# endstop_ctl.net
KiCad netlist of a schematic drawn in EAGLE
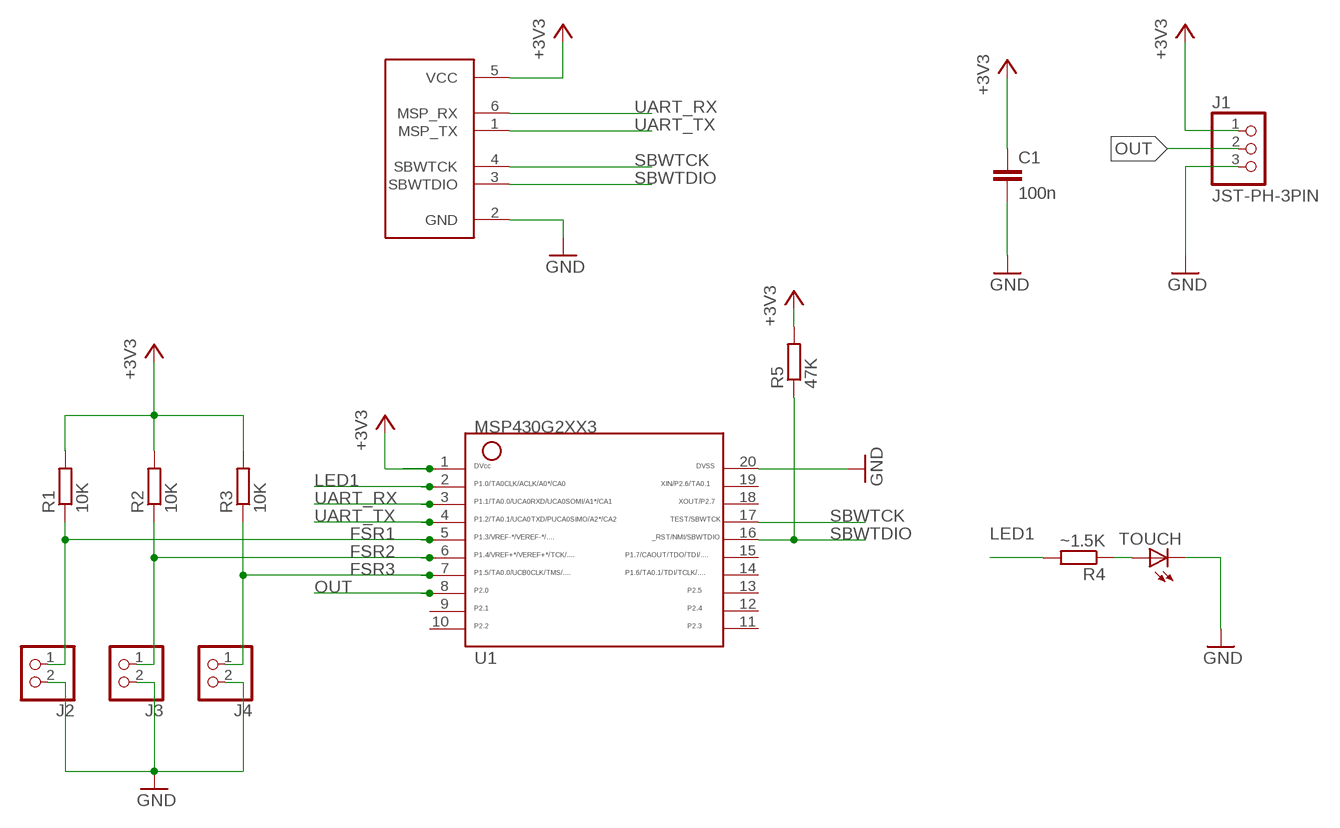
[diagram p0: schematic, sheet 1]

(export (version "E")
  (design (tool "Eeschema 10.0.6"))
  (components
    (comp (ref "C1")
      (value "100n")
      (footprint "eagle-import:C0603")
      (libsource (lib "eagle-import") (part "C-EUC0603"))
    )
    (comp (ref "J1")
      (value "JST-PH-3PIN")
      (footprint "eagle-import:JST-PH-3PIN-PTH-RA")
      (libsource (lib "eagle-import") (part "JST-PH-3PIN"))
    )
    (comp (ref "J2")
      (value "JST_2PIN-THM-RA")
      (footprint "eagle-import:JST-PH-2-THM-RA")
      (libsource (lib "eagle-import") (part "JST_2PIN-THM-RA"))
    )
    (comp (ref "J3")
      (value "JST_2PIN-THM-RA")
      (footprint "eagle-import:JST-PH-2-THM-RA")
      (libsource (lib "eagle-import") (part "JST_2PIN-THM-RA"))
    )
    (comp (ref "J4")
      (value "JST_2PIN-THM-RA")
      (footprint "eagle-import:JST-PH-2-THM-RA")
      (libsource (lib "eagle-import") (part "JST_2PIN-THM-RA"))
    )
    (comp (ref "J5")
      (value "MSP-SBWPTH")
      (footprint "eagle-import:MSP-SBW-0.05-PTH-90DEG")
      (libsource (lib "eagle-import") (part "MSP-SBWPTH"))
    )
    (comp (ref "R1")
      (value "10K")
      (footprint "eagle-import:R0603")
      (libsource (lib "eagle-import") (part "R-EU_R0603"))
    )
    (comp (ref "R2")
      (value "10K")
      (footprint "eagle-import:R0603")
      (libsource (lib "eagle-import") (part "R-EU_R0603"))
    )
    (comp (ref "R3")
      (value "10K")
      (footprint "eagle-import:R0603")
      (libsource (lib "eagle-import") (part "R-EU_R0603"))
    )
    (comp (ref "R4")
      (value "~1.5K")
      (footprint "eagle-import:R0603")
      (libsource (lib "eagle-import") (part "R-EU_R0603"))
    )
    (comp (ref "R5")
      (value "47K")
      (footprint "eagle-import:R0603")
      (libsource (lib "eagle-import") (part "R-EU_R0603"))
    )
    (comp (ref "TOUCH")
      (value "LED0603")
      (footprint "eagle-import:LED-0603")
      (libsource (lib "eagle-import") (part "LED0603"))
    )
    (comp (ref "U1")
      (value "G2XX3---PW20")
      (footprint "eagle-import:PW20")
      (libsource (lib "eagle-import") (part "G2XX3---PW20"))
    )
  )
  (nets
    (net (code "1") (name "+3V3") (class "Default")
      (node (ref "C1") (pin "1") (pinfunction "1_1") (pintype "passive"))
      (node (ref "J1") (pin "1") (pinfunction "1_1") (pintype "passive"))
      (node (ref "J5") (pin "5") (pinfunction "VCC_5") (pintype "power_in"))
      (node (ref "R1") (pin "2") (pinfunction "2_2") (pintype "passive"))
      (node (ref "R2") (pin "2") (pinfunction "2_2") (pintype "passive"))
      (node (ref "R3") (pin "2") (pinfunction "2_2") (pintype "passive"))
      (node (ref "R5") (pin "2") (pinfunction "2_2") (pintype "passive"))
      (node (ref "U1") (pin "1") (pinfunction "1_1") (pintype "bidirectional"))
    )
    (net (code "2") (name "/FSR1") (class "Default")
      (node (ref "J2") (pin "1") (pinfunction "2_1") (pintype "passive"))
      (node (ref "R1") (pin "1") (pinfunction "1_1") (pintype "passive"))
      (node (ref "U1") (pin "5") (pinfunction "5_5") (pintype "bidirectional"))
    )
    (net (code "3") (name "/FSR2") (class "Default")
      (node (ref "J3") (pin "1") (pinfunction "2_1") (pintype "passive"))
      (node (ref "R2") (pin "1") (pinfunction "1_1") (pintype "passive"))
      (node (ref "U1") (pin "6") (pinfunction "6_6") (pintype "bidirectional"))
    )
    (net (code "4") (name "/FSR3") (class "Default")
      (node (ref "J4") (pin "1") (pinfunction "2_1") (pintype "passive"))
      (node (ref "R3") (pin "1") (pinfunction "1_1") (pintype "passive"))
      (node (ref "U1") (pin "7") (pinfunction "7_7") (pintype "bidirectional"))
    )
    (net (code "5") (name "/LED1") (class "Default")
      (node (ref "R4") (pin "2") (pinfunction "2_2") (pintype "passive"))
      (node (ref "U1") (pin "2") (pinfunction "2_2") (pintype "bidirectional"))
    )
    (net (code "6") (name "/SBWTCK") (class "Default")
      (node (ref "J5") (pin "4") (pinfunction "SBWTCK_4") (pintype "bidirectional"))
      (node (ref "U1") (pin "17") (pinfunction "17_17") (pintype "bidirectional"))
    )
    (net (code "7") (name "/SBWTDIO") (class "Default")
      (node (ref "J5") (pin "3") (pinfunction "SBWTDIO_3") (pintype "bidirectional"))
      (node (ref "R5") (pin "1") (pinfunction "1_1") (pintype "passive"))
      (node (ref "U1") (pin "16") (pinfunction "16_16") (pintype "bidirectional"))
    )
    (net (code "8") (name "/UART_RX") (class "Default")
      (node (ref "J5") (pin "6") (pinfunction "MSP_RX_6") (pintype "bidirectional"))
      (node (ref "U1") (pin "3") (pinfunction "3_3") (pintype "bidirectional"))
    )
    (net (code "9") (name "/UART_TX") (class "Default")
      (node (ref "J5") (pin "1") (pinfunction "MSP_TX_1") (pintype "bidirectional"))
      (node (ref "U1") (pin "4") (pinfunction "4_4") (pintype "bidirectional"))
    )
    (net (code "10") (name "GND") (class "Default")
      (node (ref "C1") (pin "2") (pinfunction "2_2") (pintype "passive"))
      (node (ref "J1") (pin "3") (pinfunction "3_3") (pintype "passive"))
      (node (ref "J2") (pin "2") (pinfunction "1_2") (pintype "passive"))
      (node (ref "J3") (pin "2") (pinfunction "1_2") (pintype "passive"))
      (node (ref "J4") (pin "2") (pinfunction "1_2") (pintype "passive"))
      (node (ref "J5") (pin "2") (pinfunction "GND_2") (pintype "power_in"))
      (node (ref "TOUCH") (pin "C") (pinfunction "C_C") (pintype "passive"))
      (node (ref "U1") (pin "20") (pinfunction "20_20") (pintype "bidirectional"))
    )
    (net (code "11") (name "Net-(R4-Pad1)") (class "Default")
      (node (ref "R4") (pin "1") (pinfunction "1_1") (pintype "passive"))
      (node (ref "TOUCH") (pin "A") (pinfunction "A_A") (pintype "passive"))
    )
    (net (code "12") (name "OUT") (class "Default")
      (node (ref "J1") (pin "2") (pinfunction "2_2") (pintype "passive"))
      (node (ref "U1") (pin "8") (pinfunction "8_8") (pintype "bidirectional"))
    )
    (net (code "13") (name "unconnected-(U1-Pad9)") (class "Default")
      (node (ref "U1") (pin "9") (pinfunction "9_9") (pintype "bidirectional"))
    )
    (net (code "14") (name "unconnected-(U1-Pad10)") (class "Default")
      (node (ref "U1") (pin "10") (pinfunction "10_10") (pintype "bidirectional"))
    )
    (net (code "15") (name "unconnected-(U1-Pad11)") (class "Default")
      (node (ref "U1") (pin "11") (pinfunction "11_11") (pintype "bidirectional"))
    )
    (net (code "16") (name "unconnected-(U1-Pad12)") (class "Default")
      (node (ref "U1") (pin "12") (pinfunction "12_12") (pintype "bidirectional"))
    )
    (net (code "17") (name "unconnected-(U1-Pad13)") (class "Default")
      (node (ref "U1") (pin "13") (pinfunction "13_13") (pintype "bidirectional"))
    )
    (net (code "18") (name "unconnected-(U1-Pad14)") (class "Default")
      (node (ref "U1") (pin "14") (pinfunction "14_14") (pintype "bidirectional"))
    )
    (net (code "19") (name "unconnected-(U1-Pad15)") (class "Default")
      (node (ref "U1") (pin "15") (pinfunction "15_15") (pintype "bidirectional"))
    )
    (net (code "20") (name "unconnected-(U1-Pad18)") (class "Default")
      (node (ref "U1") (pin "18") (pinfunction "18_18") (pintype "bidirectional"))
    )
    (net (code "21") (name "unconnected-(U1-Pad19)") (class "Default")
      (node (ref "U1") (pin "19") (pinfunction "19_19") (pintype "bidirectional"))
    )
  )
)
